# D_INPUT.net
KiCad netlist of a schematic drawn in Altium Designer
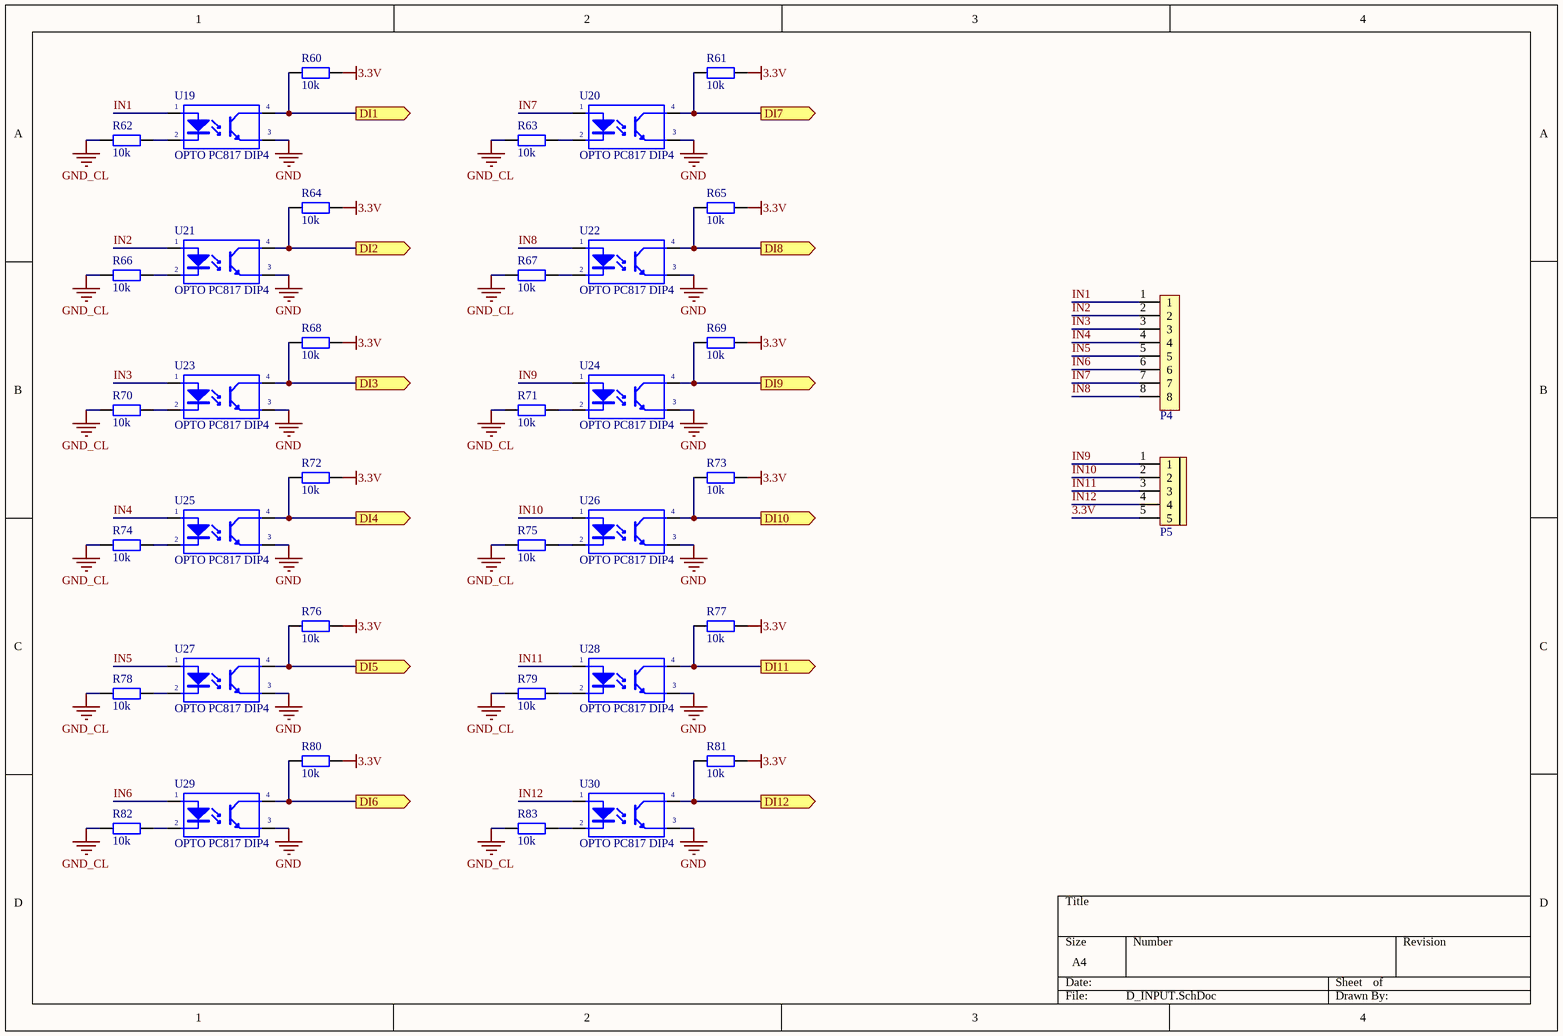
[diagram p0: D_INPUT.SchDoc]

(export (version "E")
  (design (tool "Eeschema 10.0.6"))
  (components
    (comp (ref "P4")
      (value "CON 8 EDG5.08")
      (footprint "CON 8 8EDG5.08")
      (description "Cắm")
      (libsource (lib "Altium_Lib_by_KhueNguyenCreator") (part "CON 8 EDG5.08"))
    )
    (comp (ref "P5")
      (value "CON 5 EDG5.08")
      (footprint "CON 5 5EDG5.08")
      (description "Cắm")
      (libsource (lib "Altium_Lib_by_KhueNguyenCreator") (part "CON 5 EDG5.08"))
    )
    (comp (ref "R60")
      (value "10k")
      (footprint "tro smd 0805")
      (description "Dán")
      (libsource (lib "Altium_Lib_by_KhueNguyenCreator") (part "Tro 0805 1% 10k"))
    )
    (comp (ref "R61")
      (value "10k")
      (footprint "tro smd 0805")
      (description "Dán")
      (libsource (lib "Altium_Lib_by_KhueNguyenCreator") (part "Tro 0805 1% 10k"))
    )
    (comp (ref "R62")
      (value "10k")
      (footprint "tro smd 0805")
      (description "Dán")
      (libsource (lib "Altium_Lib_by_KhueNguyenCreator") (part "Tro 0805 1% 10k"))
    )
    (comp (ref "R63")
      (value "10k")
      (footprint "tro smd 0805")
      (description "Dán")
      (libsource (lib "Altium_Lib_by_KhueNguyenCreator") (part "Tro 0805 1% 10k"))
    )
    (comp (ref "R64")
      (value "10k")
      (footprint "tro smd 0805")
      (description "Dán")
      (libsource (lib "Altium_Lib_by_KhueNguyenCreator") (part "Tro 0805 1% 10k"))
    )
    (comp (ref "R65")
      (value "10k")
      (footprint "tro smd 0805")
      (description "Dán")
      (libsource (lib "Altium_Lib_by_KhueNguyenCreator") (part "Tro 0805 1% 10k"))
    )
    (comp (ref "R66")
      (value "10k")
      (footprint "tro smd 0805")
      (description "Dán")
      (libsource (lib "Altium_Lib_by_KhueNguyenCreator") (part "Tro 0805 1% 10k"))
    )
    (comp (ref "R67")
      (value "10k")
      (footprint "tro smd 0805")
      (description "Dán")
      (libsource (lib "Altium_Lib_by_KhueNguyenCreator") (part "Tro 0805 1% 10k"))
    )
    (comp (ref "R68")
      (value "10k")
      (footprint "tro smd 0805")
      (description "Dán")
      (libsource (lib "Altium_Lib_by_KhueNguyenCreator") (part "Tro 0805 1% 10k"))
    )
    (comp (ref "R69")
      (value "10k")
      (footprint "tro smd 0805")
      (description "Dán")
      (libsource (lib "Altium_Lib_by_KhueNguyenCreator") (part "Tro 0805 1% 10k"))
    )
    (comp (ref "R70")
      (value "10k")
      (footprint "tro smd 0805")
      (description "Dán")
      (libsource (lib "Altium_Lib_by_KhueNguyenCreator") (part "Tro 0805 1% 10k"))
    )
    (comp (ref "R71")
      (value "10k")
      (footprint "tro smd 0805")
      (description "Dán")
      (libsource (lib "Altium_Lib_by_KhueNguyenCreator") (part "Tro 0805 1% 10k"))
    )
    (comp (ref "R72")
      (value "10k")
      (footprint "tro smd 0805")
      (description "Dán")
      (libsource (lib "Altium_Lib_by_KhueNguyenCreator") (part "Tro 0805 1% 10k"))
    )
    (comp (ref "R73")
      (value "10k")
      (footprint "tro smd 0805")
      (description "Dán")
      (libsource (lib "Altium_Lib_by_KhueNguyenCreator") (part "Tro 0805 1% 10k"))
    )
    (comp (ref "R74")
      (value "10k")
      (footprint "tro smd 0805")
      (description "Dán")
      (libsource (lib "Altium_Lib_by_KhueNguyenCreator") (part "Tro 0805 1% 10k"))
    )
    (comp (ref "R75")
      (value "10k")
      (footprint "tro smd 0805")
      (description "Dán")
      (libsource (lib "Altium_Lib_by_KhueNguyenCreator") (part "Tro 0805 1% 10k"))
    )
    (comp (ref "R76")
      (value "10k")
      (footprint "tro smd 0805")
      (description "Dán")
      (libsource (lib "Altium_Lib_by_KhueNguyenCreator") (part "Tro 0805 1% 10k"))
    )
    (comp (ref "R77")
      (value "10k")
      (footprint "tro smd 0805")
      (description "Dán")
      (libsource (lib "Altium_Lib_by_KhueNguyenCreator") (part "Tro 0805 1% 10k"))
    )
    (comp (ref "R78")
      (value "10k")
      (footprint "tro smd 0805")
      (description "Dán")
      (libsource (lib "Altium_Lib_by_KhueNguyenCreator") (part "Tro 0805 1% 10k"))
    )
    (comp (ref "R79")
      (value "10k")
      (footprint "tro smd 0805")
      (description "Dán")
      (libsource (lib "Altium_Lib_by_KhueNguyenCreator") (part "Tro 0805 1% 10k"))
    )
    (comp (ref "R80")
      (value "10k")
      (footprint "tro smd 0805")
      (description "Dán")
      (libsource (lib "Altium_Lib_by_KhueNguyenCreator") (part "Tro 0805 1% 10k"))
    )
    (comp (ref "R81")
      (value "10k")
      (footprint "tro smd 0805")
      (description "Dán")
      (libsource (lib "Altium_Lib_by_KhueNguyenCreator") (part "Tro 0805 1% 10k"))
    )
    (comp (ref "R82")
      (value "10k")
      (footprint "tro smd 0805")
      (description "Dán")
      (libsource (lib "Altium_Lib_by_KhueNguyenCreator") (part "Tro 0805 1% 10k"))
    )
    (comp (ref "R83")
      (value "10k")
      (footprint "tro smd 0805")
      (description "Dán")
      (libsource (lib "Altium_Lib_by_KhueNguyenCreator") (part "Tro 0805 1% 10k"))
    )
    (comp (ref "U19")
      (value "OPTO PC817 DIP4")
      (footprint "DIP4")
      (description "Single Opto")
      (libsource (lib "Altium_Lib_by_KhueNguyenCreator") (part "OPTO PC817 DIP4"))
    )
    (comp (ref "U20")
      (value "OPTO PC817 DIP4")
      (footprint "DIP4")
      (description "Single Opto")
      (libsource (lib "Altium_Lib_by_KhueNguyenCreator") (part "OPTO PC817 DIP4"))
    )
    (comp (ref "U21")
      (value "OPTO PC817 DIP4")
      (footprint "DIP4")
      (description "Single Opto")
      (libsource (lib "Altium_Lib_by_KhueNguyenCreator") (part "OPTO PC817 DIP4"))
    )
    (comp (ref "U22")
      (value "OPTO PC817 DIP4")
      (footprint "DIP4")
      (description "Single Opto")
      (libsource (lib "Altium_Lib_by_KhueNguyenCreator") (part "OPTO PC817 DIP4"))
    )
    (comp (ref "U23")
      (value "OPTO PC817 DIP4")
      (footprint "DIP4")
      (description "Single Opto")
      (libsource (lib "Altium_Lib_by_KhueNguyenCreator") (part "OPTO PC817 DIP4"))
    )
    (comp (ref "U24")
      (value "OPTO PC817 DIP4")
      (footprint "DIP4")
      (description "Single Opto")
      (libsource (lib "Altium_Lib_by_KhueNguyenCreator") (part "OPTO PC817 DIP4"))
    )
    (comp (ref "U25")
      (value "OPTO PC817 DIP4")
      (footprint "DIP4")
      (description "Single Opto")
      (libsource (lib "Altium_Lib_by_KhueNguyenCreator") (part "OPTO PC817 DIP4"))
    )
    (comp (ref "U26")
      (value "OPTO PC817 DIP4")
      (footprint "DIP4")
      (description "Single Opto")
      (libsource (lib "Altium_Lib_by_KhueNguyenCreator") (part "OPTO PC817 DIP4"))
    )
    (comp (ref "U27")
      (value "OPTO PC817 DIP4")
      (footprint "DIP4")
      (description "Single Opto")
      (libsource (lib "Altium_Lib_by_KhueNguyenCreator") (part "OPTO PC817 DIP4"))
    )
    (comp (ref "U28")
      (value "OPTO PC817 DIP4")
      (footprint "DIP4")
      (description "Single Opto")
      (libsource (lib "Altium_Lib_by_KhueNguyenCreator") (part "OPTO PC817 DIP4"))
    )
    (comp (ref "U29")
      (value "OPTO PC817 DIP4")
      (footprint "DIP4")
      (description "Single Opto")
      (libsource (lib "Altium_Lib_by_KhueNguyenCreator") (part "OPTO PC817 DIP4"))
    )
    (comp (ref "U30")
      (value "OPTO PC817 DIP4")
      (footprint "DIP4")
      (description "Single Opto")
      (libsource (lib "Altium_Lib_by_KhueNguyenCreator") (part "OPTO PC817 DIP4"))
    )
  )
  (nets
    (net (code "1") (name "/DI1") (class "Default")
      (node (ref "R60") (pin "2") (pinfunction "2_2") (pintype "passive"))
      (node (ref "U19") (pin "4") (pinfunction "C_4") (pintype "passive"))
    )
    (net (code "2") (name "/DI2") (class "Default")
      (node (ref "R64") (pin "2") (pinfunction "2_2") (pintype "passive"))
      (node (ref "U21") (pin "4") (pinfunction "C_4") (pintype "passive"))
    )
    (net (code "3") (name "/DI3") (class "Default")
      (node (ref "R68") (pin "2") (pinfunction "2_2") (pintype "passive"))
      (node (ref "U23") (pin "4") (pinfunction "C_4") (pintype "passive"))
    )
    (net (code "4") (name "/DI4") (class "Default")
      (node (ref "R72") (pin "2") (pinfunction "2_2") (pintype "passive"))
      (node (ref "U25") (pin "4") (pinfunction "C_4") (pintype "passive"))
    )
    (net (code "5") (name "/DI5") (class "Default")
      (node (ref "R76") (pin "2") (pinfunction "2_2") (pintype "passive"))
      (node (ref "U27") (pin "4") (pinfunction "C_4") (pintype "passive"))
    )
    (net (code "6") (name "/DI6") (class "Default")
      (node (ref "R80") (pin "2") (pinfunction "2_2") (pintype "passive"))
      (node (ref "U29") (pin "4") (pinfunction "C_4") (pintype "passive"))
    )
    (net (code "7") (name "/DI7") (class "Default")
      (node (ref "R61") (pin "2") (pinfunction "2_2") (pintype "passive"))
      (node (ref "U20") (pin "4") (pinfunction "C_4") (pintype "passive"))
    )
    (net (code "8") (name "/DI8") (class "Default")
      (node (ref "R65") (pin "2") (pinfunction "2_2") (pintype "passive"))
      (node (ref "U22") (pin "4") (pinfunction "C_4") (pintype "passive"))
    )
    (net (code "9") (name "/DI9") (class "Default")
      (node (ref "R69") (pin "2") (pinfunction "2_2") (pintype "passive"))
      (node (ref "U24") (pin "4") (pinfunction "C_4") (pintype "passive"))
    )
    (net (code "10") (name "/DI10") (class "Default")
      (node (ref "R73") (pin "2") (pinfunction "2_2") (pintype "passive"))
      (node (ref "U26") (pin "4") (pinfunction "C_4") (pintype "passive"))
    )
    (net (code "11") (name "/DI11") (class "Default")
      (node (ref "R77") (pin "2") (pinfunction "2_2") (pintype "passive"))
      (node (ref "U28") (pin "4") (pinfunction "C_4") (pintype "passive"))
    )
    (net (code "12") (name "/DI12") (class "Default")
      (node (ref "R81") (pin "2") (pinfunction "2_2") (pintype "passive"))
      (node (ref "U30") (pin "4") (pinfunction "C_4") (pintype "passive"))
    )
    (net (code "13") (name "/IN1") (class "Default")
      (node (ref "P4") (pin "1") (pinfunction "1_1") (pintype "passive"))
      (node (ref "U19") (pin "1") (pinfunction "A_1") (pintype "passive"))
    )
    (net (code "14") (name "/IN2") (class "Default")
      (node (ref "P4") (pin "2") (pinfunction "2_2") (pintype "passive"))
      (node (ref "U21") (pin "1") (pinfunction "A_1") (pintype "passive"))
    )
    (net (code "15") (name "/IN3") (class "Default")
      (node (ref "P4") (pin "3") (pinfunction "3_3") (pintype "passive"))
      (node (ref "U23") (pin "1") (pinfunction "A_1") (pintype "passive"))
    )
    (net (code "16") (name "/IN4") (class "Default")
      (node (ref "P4") (pin "4") (pinfunction "4_4") (pintype "passive"))
      (node (ref "U25") (pin "1") (pinfunction "A_1") (pintype "passive"))
    )
    (net (code "17") (name "/IN5") (class "Default")
      (node (ref "P4") (pin "5") (pinfunction "5_5") (pintype "passive"))
      (node (ref "U27") (pin "1") (pinfunction "A_1") (pintype "passive"))
    )
    (net (code "18") (name "/IN6") (class "Default")
      (node (ref "P4") (pin "6") (pinfunction "6_6") (pintype "passive"))
      (node (ref "U29") (pin "1") (pinfunction "A_1") (pintype "passive"))
    )
    (net (code "19") (name "/IN7") (class "Default")
      (node (ref "P4") (pin "7") (pinfunction "7_7") (pintype "passive"))
      (node (ref "U20") (pin "1") (pinfunction "A_1") (pintype "passive"))
    )
    (net (code "20") (name "/IN8") (class "Default")
      (node (ref "P4") (pin "8") (pinfunction "8_8") (pintype "passive"))
      (node (ref "U22") (pin "1") (pinfunction "A_1") (pintype "passive"))
    )
    (net (code "21") (name "/IN9") (class "Default")
      (node (ref "P5") (pin "1") (pinfunction "1_1") (pintype "passive"))
      (node (ref "U24") (pin "1") (pinfunction "A_1") (pintype "passive"))
    )
    (net (code "22") (name "/IN10") (class "Default")
      (node (ref "P5") (pin "2") (pinfunction "2_2") (pintype "passive"))
      (node (ref "U26") (pin "1") (pinfunction "A_1") (pintype "passive"))
    )
    (net (code "23") (name "/IN11") (class "Default")
      (node (ref "P5") (pin "3") (pinfunction "3_3") (pintype "passive"))
      (node (ref "U28") (pin "1") (pinfunction "A_1") (pintype "passive"))
    )
    (net (code "24") (name "/IN12") (class "Default")
      (node (ref "P5") (pin "4") (pinfunction "4_4") (pintype "passive"))
      (node (ref "U30") (pin "1") (pinfunction "A_1") (pintype "passive"))
    )
    (net (code "25") (name "3.3V") (class "Default")
      (node (ref "P5") (pin "5") (pinfunction "5_5") (pintype "passive"))
      (node (ref "R60") (pin "1") (pinfunction "1_1") (pintype "passive"))
      (node (ref "R61") (pin "1") (pinfunction "1_1") (pintype "passive"))
      (node (ref "R64") (pin "1") (pinfunction "1_1") (pintype "passive"))
      (node (ref "R65") (pin "1") (pinfunction "1_1") (pintype "passive"))
      (node (ref "R68") (pin "1") (pinfunction "1_1") (pintype "passive"))
      (node (ref "R69") (pin "1") (pinfunction "1_1") (pintype "passive"))
      (node (ref "R72") (pin "1") (pinfunction "1_1") (pintype "passive"))
      (node (ref "R73") (pin "1") (pinfunction "1_1") (pintype "passive"))
      (node (ref "R76") (pin "1") (pinfunction "1_1") (pintype "passive"))
      (node (ref "R77") (pin "1") (pinfunction "1_1") (pintype "passive"))
      (node (ref "R80") (pin "1") (pinfunction "1_1") (pintype "passive"))
      (node (ref "R81") (pin "1") (pinfunction "1_1") (pintype "passive"))
    )
    (net (code "26") (name "GND") (class "Default")
      (node (ref "U19") (pin "3") (pinfunction "E_3") (pintype "passive"))
      (node (ref "U20") (pin "3") (pinfunction "E_3") (pintype "passive"))
      (node (ref "U21") (pin "3") (pinfunction "E_3") (pintype "passive"))
      (node (ref "U22") (pin "3") (pinfunction "E_3") (pintype "passive"))
      (node (ref "U23") (pin "3") (pinfunction "E_3") (pintype "passive"))
      (node (ref "U24") (pin "3") (pinfunction "E_3") (pintype "passive"))
      (node (ref "U25") (pin "3") (pinfunction "E_3") (pintype "passive"))
      (node (ref "U26") (pin "3") (pinfunction "E_3") (pintype "passive"))
      (node (ref "U27") (pin "3") (pinfunction "E_3") (pintype "passive"))
      (node (ref "U28") (pin "3") (pinfunction "E_3") (pintype "passive"))
      (node (ref "U29") (pin "3") (pinfunction "E_3") (pintype "passive"))
      (node (ref "U30") (pin "3") (pinfunction "E_3") (pintype "passive"))
    )
    (net (code "27") (name "GND_CL") (class "Default")
      (node (ref "R62") (pin "1") (pinfunction "1_1") (pintype "passive"))
      (node (ref "R63") (pin "1") (pinfunction "1_1") (pintype "passive"))
      (node (ref "R66") (pin "1") (pinfunction "1_1") (pintype "passive"))
      (node (ref "R67") (pin "1") (pinfunction "1_1") (pintype "passive"))
      (node (ref "R70") (pin "1") (pinfunction "1_1") (pintype "passive"))
      (node (ref "R71") (pin "1") (pinfunction "1_1") (pintype "passive"))
      (node (ref "R74") (pin "1") (pinfunction "1_1") (pintype "passive"))
      (node (ref "R75") (pin "1") (pinfunction "1_1") (pintype "passive"))
      (node (ref "R78") (pin "1") (pinfunction "1_1") (pintype "passive"))
      (node (ref "R79") (pin "1") (pinfunction "1_1") (pintype "passive"))
      (node (ref "R82") (pin "1") (pinfunction "1_1") (pintype "passive"))
      (node (ref "R83") (pin "1") (pinfunction "1_1") (pintype "passive"))
    )
    (net (code "28") (name "Net-(U19-K)") (class "Default")
      (node (ref "R62") (pin "2") (pinfunction "2_2") (pintype "passive"))
      (node (ref "U19") (pin "2") (pinfunction "K_2") (pintype "passive"))
    )
    (net (code "29") (name "Net-(U20-K)") (class "Default")
      (node (ref "R63") (pin "2") (pinfunction "2_2") (pintype "passive"))
      (node (ref "U20") (pin "2") (pinfunction "K_2") (pintype "passive"))
    )
    (net (code "30") (name "Net-(U21-K)") (class "Default")
      (node (ref "R66") (pin "2") (pinfunction "2_2") (pintype "passive"))
      (node (ref "U21") (pin "2") (pinfunction "K_2") (pintype "passive"))
    )
    (net (code "31") (name "Net-(U22-K)") (class "Default")
      (node (ref "R67") (pin "2") (pinfunction "2_2") (pintype "passive"))
      (node (ref "U22") (pin "2") (pinfunction "K_2") (pintype "passive"))
    )
    (net (code "32") (name "Net-(U23-K)") (class "Default")
      (node (ref "R70") (pin "2") (pinfunction "2_2") (pintype "passive"))
      (node (ref "U23") (pin "2") (pinfunction "K_2") (pintype "passive"))
    )
    (net (code "33") (name "Net-(U24-K)") (class "Default")
      (node (ref "R71") (pin "2") (pinfunction "2_2") (pintype "passive"))
      (node (ref "U24") (pin "2") (pinfunction "K_2") (pintype "passive"))
    )
    (net (code "34") (name "Net-(U25-K)") (class "Default")
      (node (ref "R74") (pin "2") (pinfunction "2_2") (pintype "passive"))
      (node (ref "U25") (pin "2") (pinfunction "K_2") (pintype "passive"))
    )
    (net (code "35") (name "Net-(U26-K)") (class "Default")
      (node (ref "R75") (pin "2") (pinfunction "2_2") (pintype "passive"))
      (node (ref "U26") (pin "2") (pinfunction "K_2") (pintype "passive"))
    )
    (net (code "36") (name "Net-(U27-K)") (class "Default")
      (node (ref "R78") (pin "2") (pinfunction "2_2") (pintype "passive"))
      (node (ref "U27") (pin "2") (pinfunction "K_2") (pintype "passive"))
    )
    (net (code "37") (name "Net-(U28-K)") (class "Default")
      (node (ref "R79") (pin "2") (pinfunction "2_2") (pintype "passive"))
      (node (ref "U28") (pin "2") (pinfunction "K_2") (pintype "passive"))
    )
    (net (code "38") (name "Net-(U29-K)") (class "Default")
      (node (ref "R82") (pin "2") (pinfunction "2_2") (pintype "passive"))
      (node (ref "U29") (pin "2") (pinfunction "K_2") (pintype "passive"))
    )
    (net (code "39") (name "Net-(U30-K)") (class "Default")
      (node (ref "R83") (pin "2") (pinfunction "2_2") (pintype "passive"))
      (node (ref "U30") (pin "2") (pinfunction "K_2") (pintype "passive"))
    )
  )
)
